# PSU.net
KiCad netlist of a schematic drawn in Altium Designer
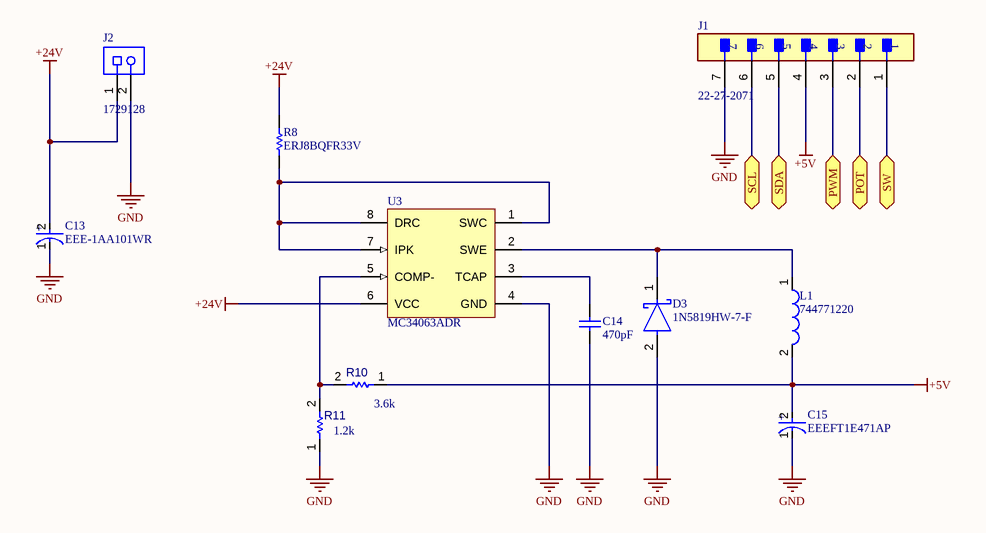
[diagram p0: PSU.SchDoc]

(export (version "E")
  (design (tool "Eeschema 10.0.6"))
  (components
    (comp (ref "C13")
      (value "EEE-1AA101WR")
      (footprint "FP-SC-MFG")
      (description "CAP ALUM 100UF 20% 10V SMD")
      (fields (field (name "TOLERANCE") "20%"))
      (libsource (lib "Altium Content Vault") (part "a00bbbee19879c290e62620ae7e47b1"))
    )
    (comp (ref "C14")
      (value "470pF")
      (footprint "CAPC1608X90X35NL10T15")
      (fields (field (name "PART NUMBER") "GRM188R71H471KA01D") (field (name "MANUFACTURER") "Murata"))
      (libsource (lib "Altium Content Vault") (part "CAP"))
    )
    (comp (ref "C15")
      (value "EEEFT1E471AP")
      (footprint "FP-FTF-MFG")
      (description "CAP ALUM 470UF 20% 25V SMD")
      (fields (field (name "VOLTAGE") "25V") (field (name "TOLERANCE") "20%"))
      (libsource (lib "Altium Content Vault") (part "a00bbbee19879c290e62620ae7e47b1"))
    )
    (comp (ref "D3")
      (value "1N5819HW-7-F")
      (footprint "FP-SOD123-IPC_B")
      (description "DIODE SCHOTTKY 40V 1A SOD123")
      (libsource (lib "Altium Content Vault") (part "1d6ec82d83fb6aee721767c19dac4b9"))
    )
    (comp (ref "J1")
      (value "22-27-2071")
      (footprint "FP-22-27-2071-MFG")
      (description "CONN HEADER VERT 7POS 2.54MM")
      (libsource (lib "Altium Content Vault") (part "5bcee6b94e1fee4be3f4cc3a650a442"))
    )
    (comp (ref "J2")
      (value "1729128")
      (footprint "PHOE-1729128-2_V")
      (description "PCB Terminal Block, 13.5 A, 400 V, 2-Pin THD, RoHS, Bulk")
      (fields (field (name "MANUFACTURER") "Phoenix Contact"))
      (libsource (lib "Altium Content Vault") (part "CN-2P-F-R2"))
    )
    (comp (ref "L1")
      (value "744771220")
      (footprint "WE-PD-L")
      (description "SMD-Shielded Power Inductor WE-PD, L = 220 µH")
      (libsource (lib "Altium Content Vault") (part "PAS-IND-INDUCTOR-2"))
    )
    (comp (ref "R8")
      (value "ERJ8BQFR33V")
      (footprint "RESC3216X70X50NL05T20")
      (fields (field (name "MANUFACTURER") "Panasonic"))
      (libsource (lib "Altium Content Vault") (part "RES"))
    )
    (comp (ref "R10")
      (value "3.6k")
      (footprint "RESC0402(1005)_L")
      (description "3.8k")
      (libsource (lib "Kariboo") (part "0R2J"))
    )
    (comp (ref "R11") (value "1.2k") (footprint "RESC0402(1005)_L") (libsource (lib "Kariboo") (part "0R2J")))
    (comp (ref "U3")
      (value "MC34063ADR")
      (footprint "D0008A_M")
      (fields (field (name "MANUFACTURER") "Texas Instruments"))
      (libsource (lib "Altium Content Vault") (part "TI-MC34063AD8"))
    )
  )
  (nets
    (net (code "1") (name "+5V") (class "Default")
      (node (ref "C15") (pin "2") (pinfunction "A_2") (pintype "passive"))
      (node (ref "J1") (pin "4") (pinfunction "4_4") (pintype "passive"))
      (node (ref "L1") (pin "2") (pinfunction "2_2") (pintype "passive"))
      (node (ref "R10") (pin "1") (pinfunction "1_1") (pintype "passive"))
    )
    (net (code "2") (name "+24V") (class "Default")
      (node (ref "C13") (pin "2") (pinfunction "A_2") (pintype "passive"))
      (node (ref "J2") (pin "1") (pinfunction "1_1") (pintype "passive"))
      (node (ref "R8") (pin "2") (pinfunction "2_2") (pintype "passive"))
      (node (ref "U3") (pin "6") (pinfunction "VCC_6") (pintype "power_in"))
    )
    (net (code "3") (name "/POT") (class "Default")
      (node (ref "J1") (pin "2") (pinfunction "2_2") (pintype "passive"))
    )
    (net (code "4") (name "/PWM") (class "Default")
      (node (ref "J1") (pin "3") (pinfunction "3_3") (pintype "passive"))
    )
    (net (code "5") (name "/SCL") (class "Default")
      (node (ref "J1") (pin "6") (pinfunction "6_6") (pintype "passive"))
    )
    (net (code "6") (name "/SDA") (class "Default")
      (node (ref "J1") (pin "5") (pinfunction "5_5") (pintype "passive"))
    )
    (net (code "7") (name "/SW") (class "Default")
      (node (ref "J1") (pin "1") (pinfunction "1_1") (pintype "passive"))
    )
    (net (code "8") (name "GND") (class "Default")
      (node (ref "C13") (pin "1") (pinfunction "C_1") (pintype "passive"))
      (node (ref "C14") (pin "1") (pinfunction "1_1") (pintype "passive"))
      (node (ref "C15") (pin "1") (pinfunction "C_1") (pintype "passive"))
      (node (ref "D3") (pin "2") (pinfunction "A_2") (pintype "passive"))
      (node (ref "J1") (pin "7") (pinfunction "7_7") (pintype "passive"))
      (node (ref "J2") (pin "2") (pinfunction "2_2") (pintype "passive"))
      (node (ref "R11") (pin "1") (pinfunction "1_1") (pintype "passive"))
      (node (ref "U3") (pin "4") (pinfunction "GND_4") (pintype "power_in"))
    )
    (net (code "9") (name "Net-(D3-C)") (class "Default")
      (node (ref "D3") (pin "1") (pinfunction "C_1") (pintype "passive"))
      (node (ref "L1") (pin "1") (pinfunction "1_1") (pintype "passive"))
      (node (ref "U3") (pin "2") (pinfunction "SWE_2") (pintype "open_emitter"))
    )
    (net (code "10") (name "Net-(U3-COMP-)") (class "Default")
      (node (ref "R10") (pin "2") (pinfunction "2_2") (pintype "passive"))
      (node (ref "R11") (pin "2") (pinfunction "2_2") (pintype "passive"))
      (node (ref "U3") (pin "5") (pinfunction "COMP-_5") (pintype "input"))
    )
    (net (code "11") (name "Net-(U3-DRC)") (class "Default")
      (node (ref "R8") (pin "1") (pinfunction "1_1") (pintype "passive"))
      (node (ref "U3") (pin "1") (pinfunction "SWC_1") (pintype "open_collector"))
      (node (ref "U3") (pin "7") (pinfunction "IPK_7") (pintype "input"))
      (node (ref "U3") (pin "8") (pinfunction "DRC_8") (pintype "open_collector"))
    )
    (net (code "12") (name "Net-(U3-TCAP)") (class "Default")
      (node (ref "C14") (pin "2") (pinfunction "2_2") (pintype "passive"))
      (node (ref "U3") (pin "3") (pinfunction "TCAP_3") (pintype "passive"))
    )
  )
)
